# 7inLED-cntr-J010130C.net
KiCad netlist of a schematic drawn in EAGLE
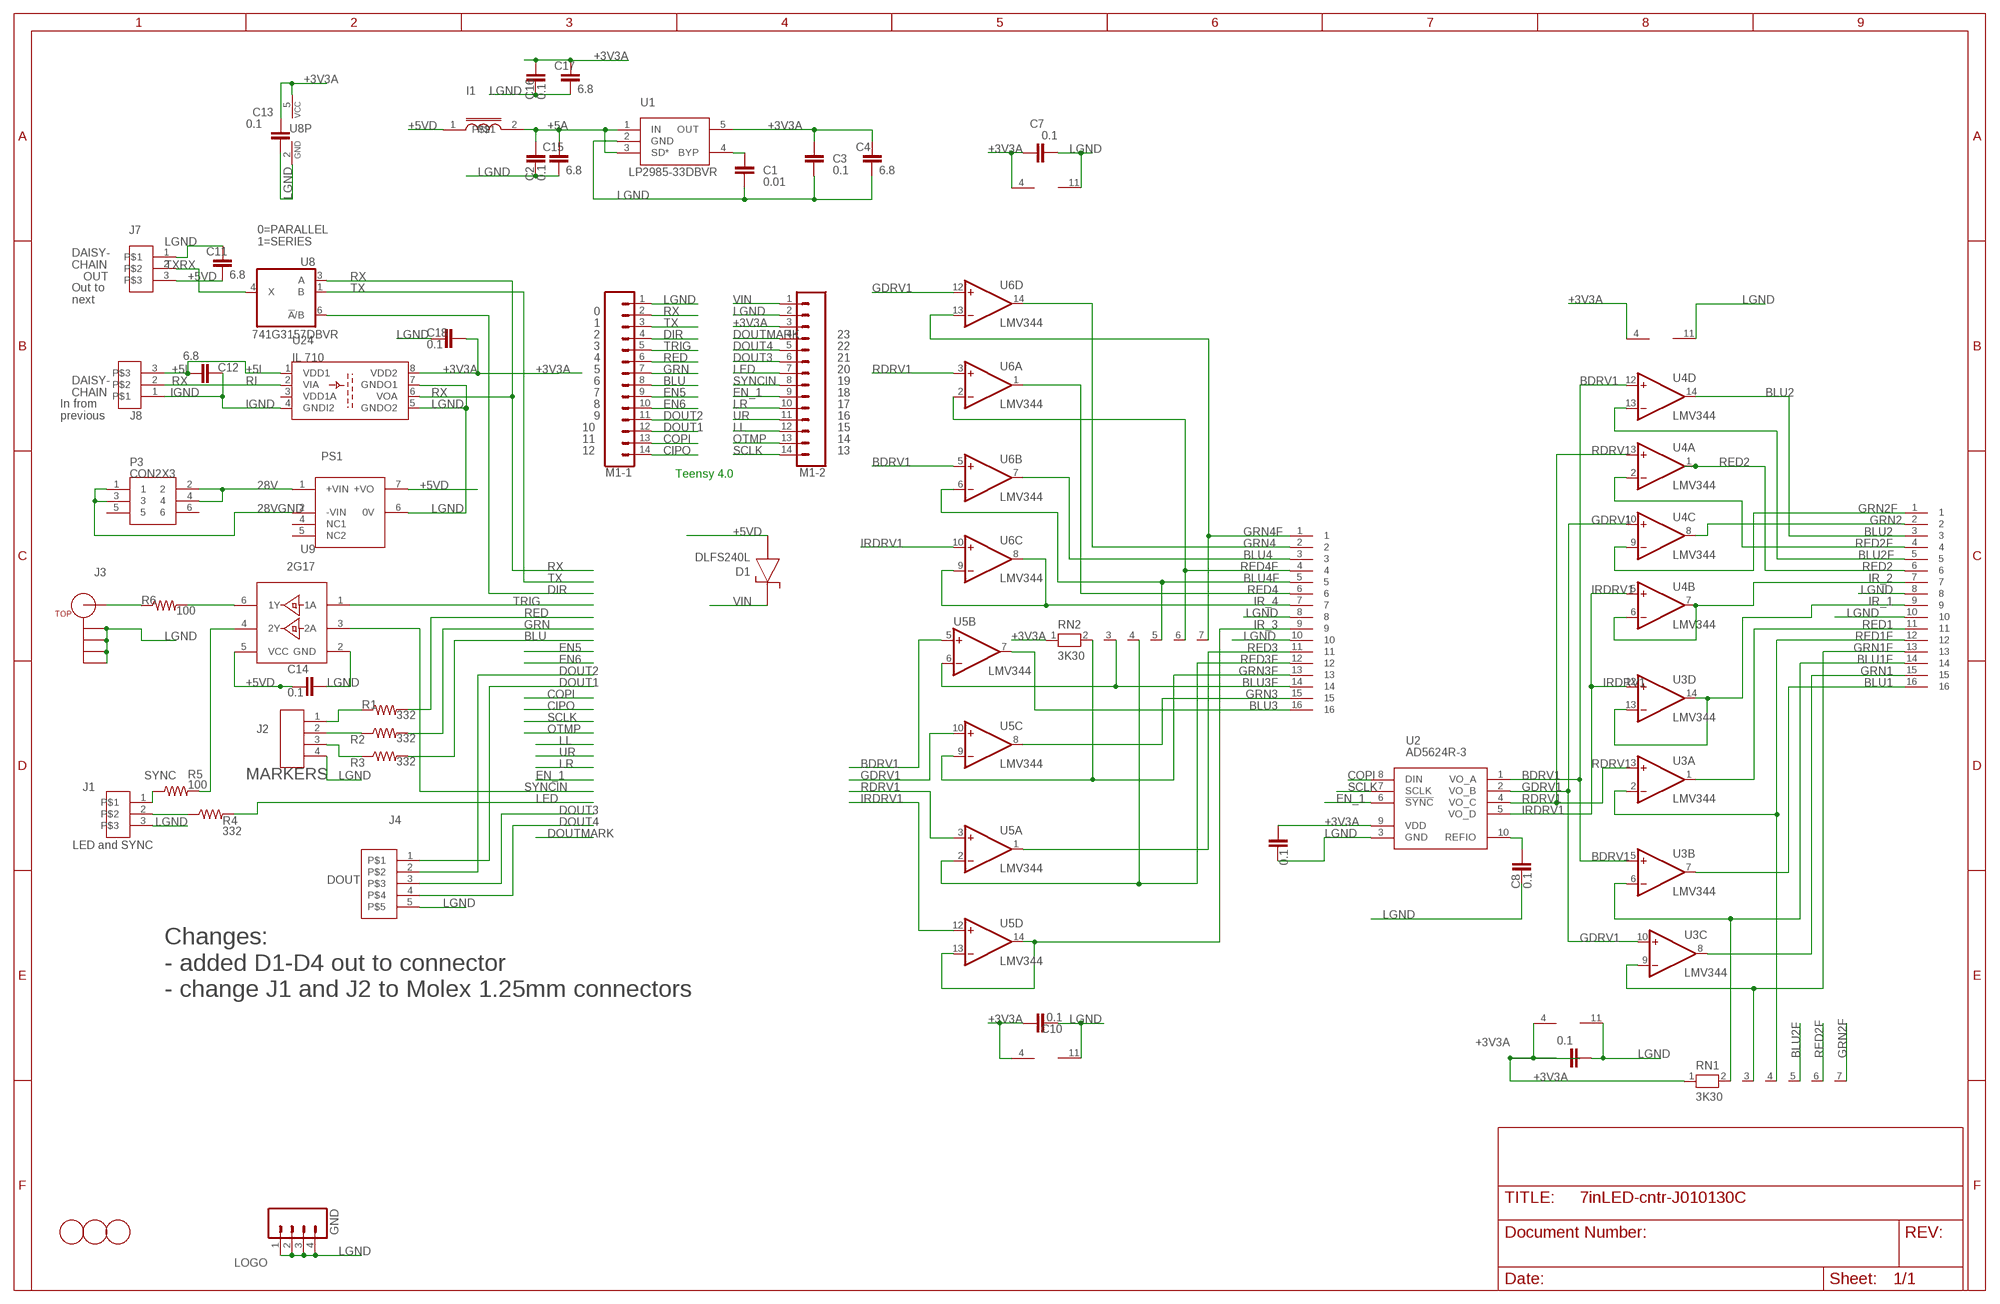
[diagram p0: schematic, sheet 1]

(export (version "E")
  (design (tool "Eeschema 10.0.6"))
  (components
    (comp (ref "C1")
      (value "0.01")
      (footprint "eagle-import:0805S")
      (libsource (lib "eagle-import") (part "CAPS0805S"))
    )
    (comp (ref "C2")
      (value "0.1")
      (footprint "eagle-import:0603S")
      (libsource (lib "eagle-import") (part "CAPS0603S"))
    )
    (comp (ref "C3")
      (value "0.1")
      (footprint "eagle-import:0603S")
      (libsource (lib "eagle-import") (part "CAPS0603S"))
    )
    (comp (ref "C4")
      (value "6.8")
      (footprint "eagle-import:1206S")
      (libsource (lib "eagle-import") (part "CAPS1206S"))
    )
    (comp (ref "C5")
      (value "0.1")
      (footprint "eagle-import:0603S")
      (libsource (lib "eagle-import") (part "CAPS0603S"))
    )
    (comp (ref "C7")
      (value "0.1")
      (footprint "eagle-import:0603S")
      (libsource (lib "eagle-import") (part "CAPS0603S"))
    )
    (comp (ref "C8")
      (value "0.1")
      (footprint "eagle-import:0603S")
      (libsource (lib "eagle-import") (part "CAPS0603S"))
    )
    (comp (ref "C9")
      (value "0.1")
      (footprint "eagle-import:0603S")
      (libsource (lib "eagle-import") (part "CAPS0603S"))
    )
    (comp (ref "C10")
      (value "0.1")
      (footprint "eagle-import:0603S")
      (libsource (lib "eagle-import") (part "CAPS0603S"))
    )
    (comp (ref "C11")
      (value "6.8")
      (footprint "eagle-import:1210S")
      (libsource (lib "eagle-import") (part "CAPS1210S"))
    )
    (comp (ref "C12")
      (value "6.8")
      (footprint "eagle-import:1210S")
      (libsource (lib "eagle-import") (part "CAPS1210S"))
    )
    (comp (ref "C13")
      (value "0.1")
      (footprint "eagle-import:0603S")
      (libsource (lib "eagle-import") (part "CAPS0603S"))
    )
    (comp (ref "C14")
      (value "0.1")
      (footprint "eagle-import:0603S")
      (libsource (lib "eagle-import") (part "CAPS0603S"))
    )
    (comp (ref "C15")
      (value "6.8")
      (footprint "eagle-import:1206S")
      (libsource (lib "eagle-import") (part "CAPS1206S"))
    )
    (comp (ref "C16")
      (value "0.1")
      (footprint "eagle-import:0603S")
      (libsource (lib "eagle-import") (part "CAPS0603S"))
    )
    (comp (ref "C17")
      (value "6.8")
      (footprint "eagle-import:1206S")
      (libsource (lib "eagle-import") (part "CAPS1206S"))
    )
    (comp (ref "C18")
      (value "0.1")
      (footprint "eagle-import:0603S")
      (libsource (lib "eagle-import") (part "CAPS0603S"))
    )
    (comp (ref "D1")
      (value "DLFS240L")
      (footprint "eagle-import:PWRDI-123")
      (libsource (lib "eagle-import") (part "DIODE_SCHOTTKYPWRDI-123"))
    )
    (comp (ref "FID1")
      (value "FIDUCIAL")
      (footprint "eagle-import:FIDUCIAL_1MM")
      (libsource (lib "eagle-import") (part "FIDUCIAL"))
    )
    (comp (ref "FID2")
      (value "FIDUCIAL")
      (footprint "eagle-import:FIDUCIAL_1MM")
      (libsource (lib "eagle-import") (part "FIDUCIAL"))
    )
    (comp (ref "FID3")
      (value "FIDUCIAL")
      (footprint "eagle-import:FIDUCIAL_1MM")
      (libsource (lib "eagle-import") (part "FIDUCIAL"))
    )
    (comp (ref "GND")
      (value "M04LOCK")
      (footprint "eagle-import:1X04_LOCK")
      (libsource (lib "eagle-import") (part "M04LOCK"))
    )
    (comp (ref "I1")
      (value "INDUCTOR0805S")
      (footprint "eagle-import:0805S")
      (libsource (lib "eagle-import") (part "INDUCTOR0805S"))
    )
    (comp (ref "J1")
      (value "CON3DF13-3TH")
      (footprint "eagle-import:DF13-3P-TH")
      (libsource (lib "eagle-import") (part "CON3DF13-3TH"))
    )
    (comp (ref "J2")
      (value "CON4DF13-4-TH")
      (footprint "eagle-import:DF13-4-TH")
      (libsource (lib "eagle-import") (part "CON4DF13-4-TH"))
    )
    (comp (ref "J3")
      (value "BNC-4PADBNC-5-1634503-1")
      (footprint "eagle-import:5-1634503-1")
      (libsource (lib "eagle-import") (part "BNC-4PADBNC-5-1634503-1"))
    )
    (comp (ref "J4")
      (value "CON5AMPMODU-5")
      (footprint "eagle-import:AMPMODU-5")
      (libsource (lib "eagle-import") (part "CON5AMPMODU-5"))
    )
    (comp (ref "J7")
      (value "CON3AMPMODU-3")
      (footprint "eagle-import:AMPMODU-3")
      (libsource (lib "eagle-import") (part "STEVES_HOME_CON3AMPMODU-3"))
    )
    (comp (ref "J8")
      (value "CON3AMPMODU-3")
      (footprint "eagle-import:AMPMODU-3")
      (libsource (lib "eagle-import") (part "STEVES_HOME_CON3AMPMODU-3"))
    )
    (comp (ref "M1-1")
      (value "CONN_14")
      (footprint "eagle-import:1X14")
      (libsource (lib "eagle-import") (part "CONN_14"))
    )
    (comp (ref "M1-2")
      (value "CONN_14")
      (footprint "eagle-import:1X14")
      (libsource (lib "eagle-import") (part "CONN_14"))
    )
    (comp (ref "P1")
      (value "CON162X8PLUG")
      (footprint "eagle-import:2X8_PLUG")
      (libsource (lib "eagle-import") (part "CON162X8PLUG"))
    )
    (comp (ref "P2")
      (value "CON162X8PLUG")
      (footprint "eagle-import:2X8_PLUG")
      (libsource (lib "eagle-import") (part "CON162X8PLUG"))
    )
    (comp (ref "P3")
      (value "CON2X3")
      (footprint "eagle-import:2X3_PLUG")
      (libsource (lib "eagle-import") (part "CON2X3"))
    )
    (comp (ref "PS1")
      (value "DC-DCISLTDN-5W")
      (footprint "eagle-import:DC-DC-TDN-5W")
      (libsource (lib "eagle-import") (part "DC-DCISLTDN-5W"))
    )
    (comp (ref "R1")
      (value "332")
      (footprint "eagle-import:0805S")
      (libsource (lib "eagle-import") (part "RESISTOR_SM0805S"))
    )
    (comp (ref "R2")
      (value "332")
      (footprint "eagle-import:0805S")
      (libsource (lib "eagle-import") (part "RESISTOR_SM0805S"))
    )
    (comp (ref "R3")
      (value "332")
      (footprint "eagle-import:0805S")
      (libsource (lib "eagle-import") (part "RESISTOR_SM0805S"))
    )
    (comp (ref "R4")
      (value "332")
      (footprint "eagle-import:0805S")
      (libsource (lib "eagle-import") (part "RESISTOR_SM0805S"))
    )
    (comp (ref "R5")
      (value "100")
      (footprint "eagle-import:0805S")
      (libsource (lib "eagle-import") (part "RESISTOR_SM0805S"))
    )
    (comp (ref "R6")
      (value "100")
      (footprint "eagle-import:0805S")
      (libsource (lib "eagle-import") (part "RESISTOR_SM0805S"))
    )
    (comp (ref "RN1")
      (value "3K30")
      (footprint "eagle-import:RN-7")
      (libsource (lib "eagle-import") (part "RN06"))
    )
    (comp (ref "RN2")
      (value "3K30")
      (footprint "eagle-import:RN-7")
      (libsource (lib "eagle-import") (part "RN06"))
    )
    (comp (ref "U$2")
      (value "JFRC-LOGOLOGO_OP")
      (footprint "eagle-import:LOGO_BMP_OP")
      (libsource (lib "eagle-import") (part "JFRC-LOGOLOGO_OP"))
    )
    (comp (ref "U1")
      (value "LP2985-33DBVR")
      (footprint "eagle-import:SOT23-5")
      (libsource (lib "eagle-import") (part "LT1761-5-SOT23"))
    )
    (comp (ref "U2")
      (value "AD5624R-3")
      (footprint "eagle-import:MSOP10")
      (libsource (lib "eagle-import") (part "AD56X4R"))
    )
    (comp (ref "U3")
      (value "LMV344")
      (footprint "eagle-import:SO14")
      (libsource (lib "eagle-import") (part "QUAD_OPAMPD"))
    )
    (comp (ref "U4")
      (value "LMV344")
      (footprint "eagle-import:SO14")
      (libsource (lib "eagle-import") (part "QUAD_OPAMPD"))
    )
    (comp (ref "U5")
      (value "LMV344")
      (footprint "eagle-import:SO14")
      (libsource (lib "eagle-import") (part "QUAD_OPAMPD"))
    )
    (comp (ref "U6")
      (value "LMV344")
      (footprint "eagle-import:SO14")
      (libsource (lib "eagle-import") (part "QUAD_OPAMPD"))
    )
    (comp (ref "U8")
      (value "741G3157DBVR")
      (footprint "eagle-import:DBV_R-PDSO-G6")
      (libsource (lib "eagle-import") (part "741G3157DBVR"))
    )
    (comp (ref "U9")
      (value "2G17")
      (footprint "eagle-import:SOT23-6")
      (libsource (lib "eagle-import") (part "2G17"))
    )
    (comp (ref "U24")
      (value "IL 710")
      (footprint "eagle-import:MSOP08")
      (libsource (lib "eagle-import") (part "ADUM1100IL710"))
    )
  )
  (nets
    (net (code "1") (name "/+3V3A") (class "Default")
      (node (ref "C10") (pin "1") (pinfunction "1_1") (pintype "passive"))
      (node (ref "C13") (pin "1") (pinfunction "1_1") (pintype "passive"))
      (node (ref "C16") (pin "1") (pinfunction "1_1") (pintype "passive"))
      (node (ref "C17") (pin "1") (pinfunction "1_1") (pintype "passive"))
      (node (ref "C18") (pin "1") (pinfunction "1_1") (pintype "passive"))
      (node (ref "C3") (pin "1") (pinfunction "1_1") (pintype "passive"))
      (node (ref "C4") (pin "1") (pinfunction "1_1") (pintype "passive"))
      (node (ref "C5") (pin "1") (pinfunction "1_1") (pintype "passive"))
      (node (ref "C7") (pin "1") (pinfunction "1_1") (pintype "passive"))
      (node (ref "C9") (pin "1") (pinfunction "1_1") (pintype "passive"))
      (node (ref "M1-2") (pin "3") (pinfunction "3_3") (pintype "passive"))
      (node (ref "RN1") (pin "1") (pinfunction "1_1") (pintype "passive"))
      (node (ref "RN2") (pin "1") (pinfunction "1_1") (pintype "passive"))
      (node (ref "U1") (pin "5") (pinfunction "OUT_5") (pintype "bidirectional"))
      (node (ref "U2") (pin "9") (pinfunction "VDD_9") (pintype "bidirectional"))
      (node (ref "U24") (pin "8") (pinfunction "VDD2_8") (pintype "input"))
      (node (ref "U3") (pin "4") (pinfunction "V+_4") (pintype "power_in"))
      (node (ref "U4") (pin "4") (pinfunction "V+_4") (pintype "power_in"))
      (node (ref "U5") (pin "4") (pinfunction "V+_4") (pintype "power_in"))
      (node (ref "U6") (pin "4") (pinfunction "V+_4") (pintype "power_in"))
      (node (ref "U8") (pin "5") (pinfunction "VCC_5") (pintype "power_in"))
    )
    (net (code "2") (name "/+5A") (class "Default")
      (node (ref "C15") (pin "1") (pinfunction "1_1") (pintype "passive"))
      (node (ref "C2") (pin "1") (pinfunction "1_1") (pintype "passive"))
      (node (ref "I1") (pin "2") (pinfunction "P$2_2") (pintype "bidirectional"))
      (node (ref "U1") (pin "1") (pinfunction "IN_1") (pintype "bidirectional"))
      (node (ref "U1") (pin "3") (pinfunction "SD*_3") (pintype "bidirectional"))
    )
    (net (code "3") (name "/+5I") (class "Default")
      (node (ref "C12") (pin "1") (pinfunction "1_1") (pintype "passive"))
      (node (ref "J8") (pin "3") (pinfunction "P$3_3") (pintype "bidirectional"))
      (node (ref "U24") (pin "1") (pinfunction "VDD1_1") (pintype "input"))
    )
    (net (code "4") (name "/+5VD") (class "Default")
      (node (ref "C11") (pin "2") (pinfunction "2_2") (pintype "passive"))
      (node (ref "C14") (pin "1") (pinfunction "1_1") (pintype "passive"))
      (node (ref "D1") (pin "A") (pinfunction "A_A") (pintype "bidirectional"))
      (node (ref "I1") (pin "1") (pinfunction "P$1_1") (pintype "bidirectional"))
      (node (ref "J7") (pin "3") (pinfunction "P$3_3") (pintype "bidirectional"))
      (node (ref "PS1") (pin "7") (pinfunction "+VO_7") (pintype "bidirectional"))
      (node (ref "U9") (pin "5") (pinfunction "VCC_5") (pintype "bidirectional"))
    )
    (net (code "5") (name "/28V") (class "Default")
      (node (ref "P3") (pin "2") (pinfunction "2_2") (pintype "bidirectional"))
      (node (ref "P3") (pin "4") (pinfunction "4_4") (pintype "bidirectional"))
      (node (ref "PS1") (pin "1") (pinfunction "+VIN_1") (pintype "bidirectional"))
    )
    (net (code "6") (name "/28VGND") (class "Default")
      (node (ref "P3") (pin "1") (pinfunction "1_1") (pintype "bidirectional"))
      (node (ref "P3") (pin "3") (pinfunction "3_3") (pintype "bidirectional"))
      (node (ref "PS1") (pin "2") (pinfunction "-VIN_2") (pintype "bidirectional"))
    )
    (net (code "7") (name "/BDRV1") (class "Default")
      (node (ref "U2") (pin "1") (pinfunction "VO_A_1") (pintype "bidirectional"))
      (node (ref "U3") (pin "5") (pinfunction "+IN_5") (pintype "input"))
      (node (ref "U4") (pin "12") (pinfunction "+IN_12") (pintype "input"))
      (node (ref "U5") (pin "5") (pinfunction "+IN_5") (pintype "input"))
      (node (ref "U6") (pin "5") (pinfunction "+IN_5") (pintype "input"))
    )
    (net (code "8") (name "/BLU") (class "Default")
      (node (ref "M1-1") (pin "8") (pinfunction "8_8") (pintype "passive"))
      (node (ref "R3") (pin "2") (pinfunction "2_2") (pintype "passive"))
    )
    (net (code "9") (name "/BLU1") (class "Default")
      (node (ref "P1") (pin "16") (pinfunction "16_16") (pintype "bidirectional"))
      (node (ref "U3") (pin "7") (pinfunction "OUT_7") (pintype "output"))
    )
    (net (code "10") (name "/BLU1F") (class "Default")
      (node (ref "P1") (pin "14") (pinfunction "14_14") (pintype "bidirectional"))
      (node (ref "RN1") (pin "2") (pinfunction "2_2") (pintype "passive"))
      (node (ref "U3") (pin "6") (pinfunction "-IN_6") (pintype "input"))
    )
    (net (code "11") (name "/BLU2") (class "Default")
      (node (ref "P1") (pin "3") (pinfunction "3_3") (pintype "bidirectional"))
      (node (ref "U4") (pin "14") (pinfunction "OUT_14") (pintype "output"))
    )
    (net (code "12") (name "/BLU2F") (class "Default")
      (node (ref "P1") (pin "5") (pinfunction "5_5") (pintype "bidirectional"))
      (node (ref "RN1") (pin "5") (pinfunction "5_5") (pintype "passive"))
      (node (ref "U4") (pin "13") (pinfunction "-IN_13") (pintype "input"))
    )
    (net (code "13") (name "/BLU3") (class "Default")
      (node (ref "P2") (pin "16") (pinfunction "16_16") (pintype "bidirectional"))
      (node (ref "U5") (pin "7") (pinfunction "OUT_7") (pintype "output"))
    )
    (net (code "14") (name "/BLU3F") (class "Default")
      (node (ref "P2") (pin "14") (pinfunction "14_14") (pintype "bidirectional"))
      (node (ref "RN2") (pin "3") (pinfunction "3_3") (pintype "passive"))
      (node (ref "U5") (pin "6") (pinfunction "-IN_6") (pintype "input"))
    )
    (net (code "15") (name "/BLU4") (class "Default")
      (node (ref "P2") (pin "3") (pinfunction "3_3") (pintype "bidirectional"))
      (node (ref "U6") (pin "7") (pinfunction "OUT_7") (pintype "output"))
    )
    (net (code "16") (name "/BLU4F") (class "Default")
      (node (ref "P2") (pin "5") (pinfunction "5_5") (pintype "bidirectional"))
      (node (ref "RN2") (pin "5") (pinfunction "5_5") (pintype "passive"))
      (node (ref "U6") (pin "6") (pinfunction "-IN_6") (pintype "input"))
    )
    (net (code "17") (name "/CIPO") (class "Default")
      (node (ref "M1-1") (pin "14") (pinfunction "14_14") (pintype "passive"))
    )
    (net (code "18") (name "/COPI") (class "Default")
      (node (ref "M1-1") (pin "13") (pinfunction "13_13") (pintype "passive"))
      (node (ref "U2") (pin "8") (pinfunction "DIN_8") (pintype "bidirectional"))
    )
    (net (code "19") (name "/DIR") (class "Default")
      (node (ref "M1-1") (pin "4") (pinfunction "4_4") (pintype "passive"))
      (node (ref "U8") (pin "6") (pinfunction "~{A}/B_6") (pintype "input"))
    )
    (net (code "20") (name "/DOUT1") (class "Default")
      (node (ref "J4") (pin "1") (pinfunction "P$1_1") (pintype "bidirectional"))
      (node (ref "M1-1") (pin "12") (pinfunction "12_12") (pintype "passive"))
    )
    (net (code "21") (name "/DOUT2") (class "Default")
      (node (ref "J4") (pin "2") (pinfunction "P$2_2") (pintype "bidirectional"))
      (node (ref "M1-1") (pin "11") (pinfunction "11_11") (pintype "passive"))
    )
    (net (code "22") (name "/DOUT3") (class "Default")
      (node (ref "J4") (pin "3") (pinfunction "P$3_3") (pintype "bidirectional"))
      (node (ref "M1-2") (pin "6") (pinfunction "6_6") (pintype "passive"))
    )
    (net (code "23") (name "/DOUT4") (class "Default")
      (node (ref "J4") (pin "4") (pinfunction "P$4_4") (pintype "bidirectional"))
      (node (ref "M1-2") (pin "5") (pinfunction "5_5") (pintype "passive"))
    )
    (net (code "24") (name "/DOUTMARK") (class "Default")
      (node (ref "M1-2") (pin "4") (pinfunction "4_4") (pintype "passive"))
    )
    (net (code "25") (name "/EN5") (class "Default")
      (node (ref "M1-1") (pin "9") (pinfunction "9_9") (pintype "passive"))
    )
    (net (code "26") (name "/EN6") (class "Default")
      (node (ref "M1-1") (pin "10") (pinfunction "10_10") (pintype "passive"))
    )
    (net (code "27") (name "/EN_1") (class "Default")
      (node (ref "M1-2") (pin "9") (pinfunction "9_9") (pintype "passive"))
      (node (ref "U2") (pin "6") (pinfunction "~{SYNC}_6") (pintype "bidirectional"))
    )
    (net (code "28") (name "/GDRV1") (class "Default")
      (node (ref "U2") (pin "2") (pinfunction "VO_B_2") (pintype "bidirectional"))
      (node (ref "U3") (pin "10") (pinfunction "+IN_10") (pintype "input"))
      (node (ref "U4") (pin "10") (pinfunction "+IN_10") (pintype "input"))
      (node (ref "U5") (pin "10") (pinfunction "+IN_10") (pintype "input"))
      (node (ref "U6") (pin "12") (pinfunction "+IN_12") (pintype "input"))
    )
    (net (code "29") (name "/GRN") (class "Default")
      (node (ref "M1-1") (pin "7") (pinfunction "7_7") (pintype "passive"))
      (node (ref "R2") (pin "2") (pinfunction "2_2") (pintype "passive"))
    )
    (net (code "30") (name "/GRN1") (class "Default")
      (node (ref "P1") (pin "15") (pinfunction "15_15") (pintype "bidirectional"))
      (node (ref "U3") (pin "8") (pinfunction "OUT_8") (pintype "output"))
    )
    (net (code "31") (name "/GRN1F") (class "Default")
      (node (ref "P1") (pin "13") (pinfunction "13_13") (pintype "bidirectional"))
      (node (ref "RN1") (pin "3") (pinfunction "3_3") (pintype "passive"))
      (node (ref "U3") (pin "9") (pinfunction "-IN_9") (pintype "input"))
    )
    (net (code "32") (name "/GRN2") (class "Default")
      (node (ref "P1") (pin "2") (pinfunction "2_2") (pintype "bidirectional"))
      (node (ref "U4") (pin "8") (pinfunction "OUT_8") (pintype "output"))
    )
    (net (code "33") (name "/GRN2F") (class "Default")
      (node (ref "P1") (pin "1") (pinfunction "1_1") (pintype "bidirectional"))
      (node (ref "RN1") (pin "7") (pinfunction "7_7") (pintype "passive"))
      (node (ref "U4") (pin "9") (pinfunction "-IN_9") (pintype "input"))
    )
    (net (code "34") (name "/GRN3") (class "Default")
      (node (ref "P2") (pin "15") (pinfunction "15_15") (pintype "bidirectional"))
      (node (ref "U5") (pin "8") (pinfunction "OUT_8") (pintype "output"))
    )
    (net (code "35") (name "/GRN3F") (class "Default")
      (node (ref "P2") (pin "13") (pinfunction "13_13") (pintype "bidirectional"))
      (node (ref "RN2") (pin "2") (pinfunction "2_2") (pintype "passive"))
      (node (ref "U5") (pin "9") (pinfunction "-IN_9") (pintype "input"))
    )
    (net (code "36") (name "/GRN4") (class "Default")
      (node (ref "P2") (pin "2") (pinfunction "2_2") (pintype "bidirectional"))
      (node (ref "U6") (pin "14") (pinfunction "OUT_14") (pintype "output"))
    )
    (net (code "37") (name "/GRN4F") (class "Default")
      (node (ref "P2") (pin "1") (pinfunction "1_1") (pintype "bidirectional"))
      (node (ref "RN2") (pin "7") (pinfunction "7_7") (pintype "passive"))
      (node (ref "U6") (pin "13") (pinfunction "-IN_13") (pintype "input"))
    )
    (net (code "38") (name "/IGND") (class "Default")
      (node (ref "C12") (pin "2") (pinfunction "2_2") (pintype "passive"))
      (node (ref "J8") (pin "1") (pinfunction "P$1_1") (pintype "bidirectional"))
      (node (ref "U24") (pin "4") (pinfunction "GNDI2_4") (pintype "input"))
    )
    (net (code "39") (name "/IRDRV1") (class "Default")
      (node (ref "U2") (pin "5") (pinfunction "VO_D_5") (pintype "bidirectional"))
      (node (ref "U3") (pin "12") (pinfunction "+IN_12") (pintype "input"))
      (node (ref "U4") (pin "5") (pinfunction "+IN_5") (pintype "input"))
      (node (ref "U5") (pin "12") (pinfunction "+IN_12") (pintype "input"))
      (node (ref "U6") (pin "10") (pinfunction "+IN_10") (pintype "input"))
    )
    (net (code "40") (name "/IR_1") (class "Default")
      (node (ref "P1") (pin "9") (pinfunction "9_9") (pintype "bidirectional"))
      (node (ref "U3") (pin "13") (pinfunction "-IN_13") (pintype "input"))
      (node (ref "U3") (pin "14") (pinfunction "OUT_14") (pintype "output"))
    )
    (net (code "41") (name "/IR_2") (class "Default")
      (node (ref "P1") (pin "7") (pinfunction "7_7") (pintype "bidirectional"))
      (node (ref "U4") (pin "6") (pinfunction "-IN_6") (pintype "input"))
      (node (ref "U4") (pin "7") (pinfunction "OUT_7") (pintype "output"))
    )
    (net (code "42") (name "/IR_3") (class "Default")
      (node (ref "P2") (pin "9") (pinfunction "9_9") (pintype "bidirectional"))
      (node (ref "U5") (pin "13") (pinfunction "-IN_13") (pintype "input"))
      (node (ref "U5") (pin "14") (pinfunction "OUT_14") (pintype "output"))
    )
    (net (code "43") (name "/IR_4") (class "Default")
      (node (ref "P2") (pin "7") (pinfunction "7_7") (pintype "bidirectional"))
      (node (ref "U6") (pin "8") (pinfunction "OUT_8") (pintype "output"))
      (node (ref "U6") (pin "9") (pinfunction "-IN_9") (pintype "input"))
    )
    (net (code "44") (name "/LED") (class "Default")
      (node (ref "M1-2") (pin "7") (pinfunction "7_7") (pintype "passive"))
      (node (ref "R4") (pin "2") (pinfunction "2_2") (pintype "passive"))
    )
    (net (code "45") (name "/LGND") (class "Default")
      (node (ref "C1") (pin "2") (pinfunction "2_2") (pintype "passive"))
      (node (ref "C10") (pin "2") (pinfunction "2_2") (pintype "passive"))
      (node (ref "C11") (pin "1") (pinfunction "1_1") (pintype "passive"))
      (node (ref "C13") (pin "2") (pinfunction "2_2") (pintype "passive"))
      (node (ref "C14") (pin "2") (pinfunction "2_2") (pintype "passive"))
      (node (ref "C15") (pin "2") (pinfunction "2_2") (pintype "passive"))
      (node (ref "C16") (pin "2") (pinfunction "2_2") (pintype "passive"))
      (node (ref "C17") (pin "2") (pinfunction "2_2") (pintype "passive"))
      (node (ref "C18") (pin "2") (pinfunction "2_2") (pintype "passive"))
      (node (ref "C2") (pin "2") (pinfunction "2_2") (pintype "passive"))
      (node (ref "C3") (pin "2") (pinfunction "2_2") (pintype "passive"))
      (node (ref "C4") (pin "2") (pinfunction "2_2") (pintype "passive"))
      (node (ref "C5") (pin "2") (pinfunction "2_2") (pintype "passive"))
      (node (ref "C7") (pin "2") (pinfunction "2_2") (pintype "passive"))
      (node (ref "C8") (pin "2") (pinfunction "2_2") (pintype "passive"))
      (node (ref "C9") (pin "2") (pinfunction "2_2") (pintype "passive"))
      (node (ref "GND") (pin "1") (pinfunction "1_1") (pintype "passive"))
      (node (ref "GND") (pin "2") (pinfunction "2_2") (pintype "passive"))
      (node (ref "GND") (pin "3") (pinfunction "3_3") (pintype "passive"))
      (node (ref "GND") (pin "4") (pinfunction "4_4") (pintype "passive"))
      (node (ref "J1") (pin "3") (pinfunction "P$3_3") (pintype "bidirectional"))
      (node (ref "J2") (pin "4") (pinfunction "P$4_4") (pintype "bidirectional"))
      (node (ref "J3") (pin "2A") (pinfunction "S1_2A") (pintype "bidirectional"))
      (node (ref "J3") (pin "2B") (pinfunction "S2_2B") (pintype "bidirectional"))
      (node (ref "J3") (pin "2C") (pinfunction "S3_2C") (pintype "bidirectional"))
      (node (ref "J3") (pin "2D") (pinfunction "S4_2D") (pintype "bidirectional"))
      (node (ref "J4") (pin "5") (pinfunction "P$5_5") (pintype "bidirectional"))
      (node (ref "J7") (pin "1") (pinfunction "P$1_1") (pintype "bidirectional"))
      (node (ref "M1-1") (pin "1") (pinfunction "1_1") (pintype "passive"))
      (node (ref "M1-2") (pin "2") (pinfunction "2_2") (pintype "passive"))
      (node (ref "P1") (pin "10") (pinfunction "10_10") (pintype "bidirectional"))
      (node (ref "P1") (pin "8") (pinfunction "8_8") (pintype "bidirectional"))
      (node (ref "P2") (pin "10") (pinfunction "10_10") (pintype "bidirectional"))
      (node (ref "P2") (pin "8") (pinfunction "8_8") (pintype "bidirectional"))
      (node (ref "PS1") (pin "6") (pinfunction "0V_6") (pintype "bidirectional"))
      (node (ref "U1") (pin "2") (pinfunction "GND_2") (pintype "bidirectional"))
      (node (ref "U2") (pin "3") (pinfunction "GND_3") (pintype "bidirectional"))
      (node (ref "U24") (pin "5") (pinfunction "GNDO2_5") (pintype "input"))
      (node (ref "U24") (pin "7") (pinfunction "GNDO1_7") (pintype "input"))
      (node (ref "U3") (pin "11") (pinfunction "V-_11") (pintype "power_in"))
      (node (ref "U4") (pin "11") (pinfunction "V-_11") (pintype "power_in"))
      (node (ref "U5") (pin "11") (pinfunction "V-_11") (pintype "power_in"))
      (node (ref "U6") (pin "11") (pinfunction "V-_11") (pintype "power_in"))
      (node (ref "U8") (pin "2") (pinfunction "GND_2") (pintype "power_in"))
      (node (ref "U9") (pin "2") (pinfunction "GND_2") (pintype "bidirectional"))
    )
    (net (code "46") (name "/LL") (class "Default")
      (node (ref "M1-2") (pin "12") (pinfunction "12_12") (pintype "passive"))
    )
    (net (code "47") (name "/LR") (class "Default")
      (node (ref "M1-2") (pin "10") (pinfunction "10_10") (pintype "passive"))
    )
    (net (code "48") (name "/OTMP") (class "Default")
      (node (ref "M1-2") (pin "13") (pinfunction "13_13") (pintype "passive"))
    )
    (net (code "49") (name "/RDRV1") (class "Default")
      (node (ref "U2") (pin "4") (pinfunction "VO_C_4") (pintype "bidirectional"))
      (node (ref "U3") (pin "3") (pinfunction "+IN_3") (pintype "input"))
      (node (ref "U4") (pin "3") (pinfunction "+IN_3") (pintype "input"))
      (node (ref "U5") (pin "3") (pinfunction "+IN_3") (pintype "input"))
      (node (ref "U6") (pin "3") (pinfunction "+IN_3") (pintype "input"))
    )
    (net (code "50") (name "/RED") (class "Default")
      (node (ref "M1-1") (pin "6") (pinfunction "6_6") (pintype "passive"))
      (node (ref "R1") (pin "2") (pinfunction "2_2") (pintype "passive"))
    )
    (net (code "51") (name "/RED1") (class "Default")
      (node (ref "P1") (pin "11") (pinfunction "11_11") (pintype "bidirectional"))
      (node (ref "U3") (pin "1") (pinfunction "OUT_1") (pintype "output"))
    )
    (net (code "52") (name "/RED1F") (class "Default")
      (node (ref "P1") (pin "12") (pinfunction "12_12") (pintype "bidirectional"))
      (node (ref "RN1") (pin "4") (pinfunction "4_4") (pintype "passive"))
      (node (ref "U3") (pin "2") (pinfunction "-IN_2") (pintype "input"))
    )
    (net (code "53") (name "/RED2") (class "Default")
      (node (ref "P1") (pin "6") (pinfunction "6_6") (pintype "bidirectional"))
      (node (ref "U4") (pin "1") (pinfunction "OUT_1") (pintype "output"))
    )
    (net (code "54") (name "/RED2F") (class "Default")
      (node (ref "P1") (pin "4") (pinfunction "4_4") (pintype "bidirectional"))
      (node (ref "RN1") (pin "6") (pinfunction "6_6") (pintype "passive"))
      (node (ref "U4") (pin "2") (pinfunction "-IN_2") (pintype "input"))
    )
    (net (code "55") (name "/RED3") (class "Default")
      (node (ref "P2") (pin "11") (pinfunction "11_11") (pintype "bidirectional"))
      (node (ref "U5") (pin "1") (pinfunction "OUT_1") (pintype "output"))
    )
    (net (code "56") (name "/RED3F") (class "Default")
      (node (ref "P2") (pin "12") (pinfunction "12_12") (pintype "bidirectional"))
      (node (ref "RN2") (pin "4") (pinfunction "4_4") (pintype "passive"))
      (node (ref "U5") (pin "2") (pinfunction "-IN_2") (pintype "input"))
    )
    (net (code "57") (name "/RED4") (class "Default")
      (node (ref "P2") (pin "6") (pinfunction "6_6") (pintype "bidirectional"))
      (node (ref "U6") (pin "1") (pinfunction "OUT_1") (pintype "output"))
    )
    (net (code "58") (name "/RED4F") (class "Default")
      (node (ref "P2") (pin "4") (pinfunction "4_4") (pintype "bidirectional"))
      (node (ref "RN2") (pin "6") (pinfunction "6_6") (pintype "passive"))
      (node (ref "U6") (pin "2") (pinfunction "-IN_2") (pintype "input"))
    )
    (net (code "59") (name "/RI") (class "Default")
      (node (ref "J8") (pin "2") (pinfunction "P$2_2") (pintype "bidirectional"))
      (node (ref "U24") (pin "2") (pinfunction "VIA_2") (pintype "input"))
    )
    (net (code "60") (name "/RX") (class "Default")
      (node (ref "M1-1") (pin "2") (pinfunction "2_2") (pintype "passive"))
      (node (ref "U24") (pin "6") (pinfunction "VOA_6") (pintype "bidirectional"))
      (node (ref "U8") (pin "3") (pinfunction "A_3") (pintype "bidirectional"))
    )
    (net (code "61") (name "/SCLK") (class "Default")
      (node (ref "M1-2") (pin "14") (pinfunction "14_14") (pintype "passive"))
      (node (ref "U2") (pin "7") (pinfunction "SCLK_7") (pintype "bidirectional"))
    )
    (net (code "62") (name "/SYNC") (class "Default")
      (node (ref "J1") (pin "1") (pinfunction "P$1_1") (pintype "bidirectional"))
      (node (ref "R5") (pin "1") (pinfunction "1_1") (pintype "passive"))
    )
    (net (code "63") (name "/SYNCIN") (class "Default")
      (node (ref "M1-2") (pin "8") (pinfunction "8_8") (pintype "passive"))
      (node (ref "U9") (pin "3") (pinfunction "2A_3") (pintype "bidirectional"))
    )
    (net (code "64") (name "/TRIG") (class "Default")
      (node (ref "M1-1") (pin "5") (pinfunction "5_5") (pintype "passive"))
      (node (ref "U9") (pin "1") (pinfunction "1A_1") (pintype "bidirectional"))
    )
    (net (code "65") (name "/TX") (class "Default")
      (node (ref "M1-1") (pin "3") (pinfunction "3_3") (pintype "passive"))
      (node (ref "U8") (pin "1") (pinfunction "B_1") (pintype "bidirectional"))
    )
    (net (code "66") (name "/TXRX") (class "Default")
      (node (ref "J7") (pin "2") (pinfunction "P$2_2") (pintype "bidirectional"))
      (node (ref "U8") (pin "4") (pinfunction "X_4") (pintype "bidirectional"))
    )
    (net (code "67") (name "/UR") (class "Default")
      (node (ref "M1-2") (pin "11") (pinfunction "11_11") (pintype "passive"))
    )
    (net (code "68") (name "/VIN") (class "Default")
      (node (ref "D1") (pin "K") (pinfunction "K_K") (pintype "bidirectional"))
      (node (ref "M1-2") (pin "1") (pinfunction "1_1") (pintype "passive"))
    )
    (net (code "69") (name "Net-(J1-P$2)") (class "Default")
      (node (ref "J1") (pin "2") (pinfunction "P$2_2") (pintype "bidirectional"))
      (node (ref "R4") (pin "1") (pinfunction "1_1") (pintype "passive"))
    )
    (net (code "70") (name "Net-(J2-P$1)") (class "Default")
      (node (ref "J2") (pin "1") (pinfunction "P$1_1") (pintype "bidirectional"))
      (node (ref "R1") (pin "1") (pinfunction "1_1") (pintype "passive"))
    )
    (net (code "71") (name "Net-(J2-P$2)") (class "Default")
      (node (ref "J2") (pin "2") (pinfunction "P$2_2") (pintype "bidirectional"))
      (node (ref "R2") (pin "1") (pinfunction "1_1") (pintype "passive"))
    )
    (net (code "72") (name "Net-(J2-P$3)") (class "Default")
      (node (ref "J2") (pin "3") (pinfunction "P$3_3") (pintype "bidirectional"))
      (node (ref "R3") (pin "1") (pinfunction "1_1") (pintype "passive"))
    )
    (net (code "73") (name "Net-(J3-C)") (class "Default")
      (node (ref "J3") (pin "1") (pinfunction "C_1") (pintype "bidirectional"))
      (node (ref "R6") (pin "1") (pinfunction "1_1") (pintype "passive"))
    )
    (net (code "74") (name "Net-(U1-BYP)") (class "Default")
      (node (ref "C1") (pin "1") (pinfunction "1_1") (pintype "passive"))
      (node (ref "U1") (pin "4") (pinfunction "BYP_4") (pintype "bidirectional"))
    )
    (net (code "75") (name "Net-(U2-REFIO)") (class "Default")
      (node (ref "C8") (pin "1") (pinfunction "1_1") (pintype "passive"))
      (node (ref "U2") (pin "10") (pinfunction "REFIO_10") (pintype "bidirectional"))
    )
    (net (code "76") (name "Net-(U9-1Y)") (class "Default")
      (node (ref "R6") (pin "2") (pinfunction "2_2") (pintype "passive"))
      (node (ref "U9") (pin "6") (pinfunction "1Y_6") (pintype "bidirectional"))
    )
    (net (code "77") (name "Net-(U9-2Y)") (class "Default")
      (node (ref "R5") (pin "2") (pinfunction "2_2") (pintype "passive"))
      (node (ref "U9") (pin "4") (pinfunction "2Y_4") (pintype "bidirectional"))
    )
    (net (code "78") (name "unconnected-(P3-Pad5)") (class "Default")
      (node (ref "P3") (pin "5") (pinfunction "5_5") (pintype "bidirectional"))
    )
    (net (code "79") (name "unconnected-(P3-Pad6)") (class "Default")
      (node (ref "P3") (pin "6") (pinfunction "6_6") (pintype "bidirectional"))
    )
    (net (code "80") (name "unconnected-(PS1-NC1-Pad4)") (class "Default")
      (node (ref "PS1") (pin "4") (pinfunction "NC1_4") (pintype "bidirectional"))
    )
    (net (code "81") (name "unconnected-(PS1-NC2-Pad5)") (class "Default")
      (node (ref "PS1") (pin "5") (pinfunction "NC2_5") (pintype "bidirectional"))
    )
    (net (code "82") (name "unconnected-(U24-VDD1A-Pad3)") (class "Default")
      (node (ref "U24") (pin "3") (pinfunction "VDD1A_3") (pintype "input"))
    )
  )
)
